# ModulWRM1470.net
KiCad netlist of a schematic drawn in Altium Designer
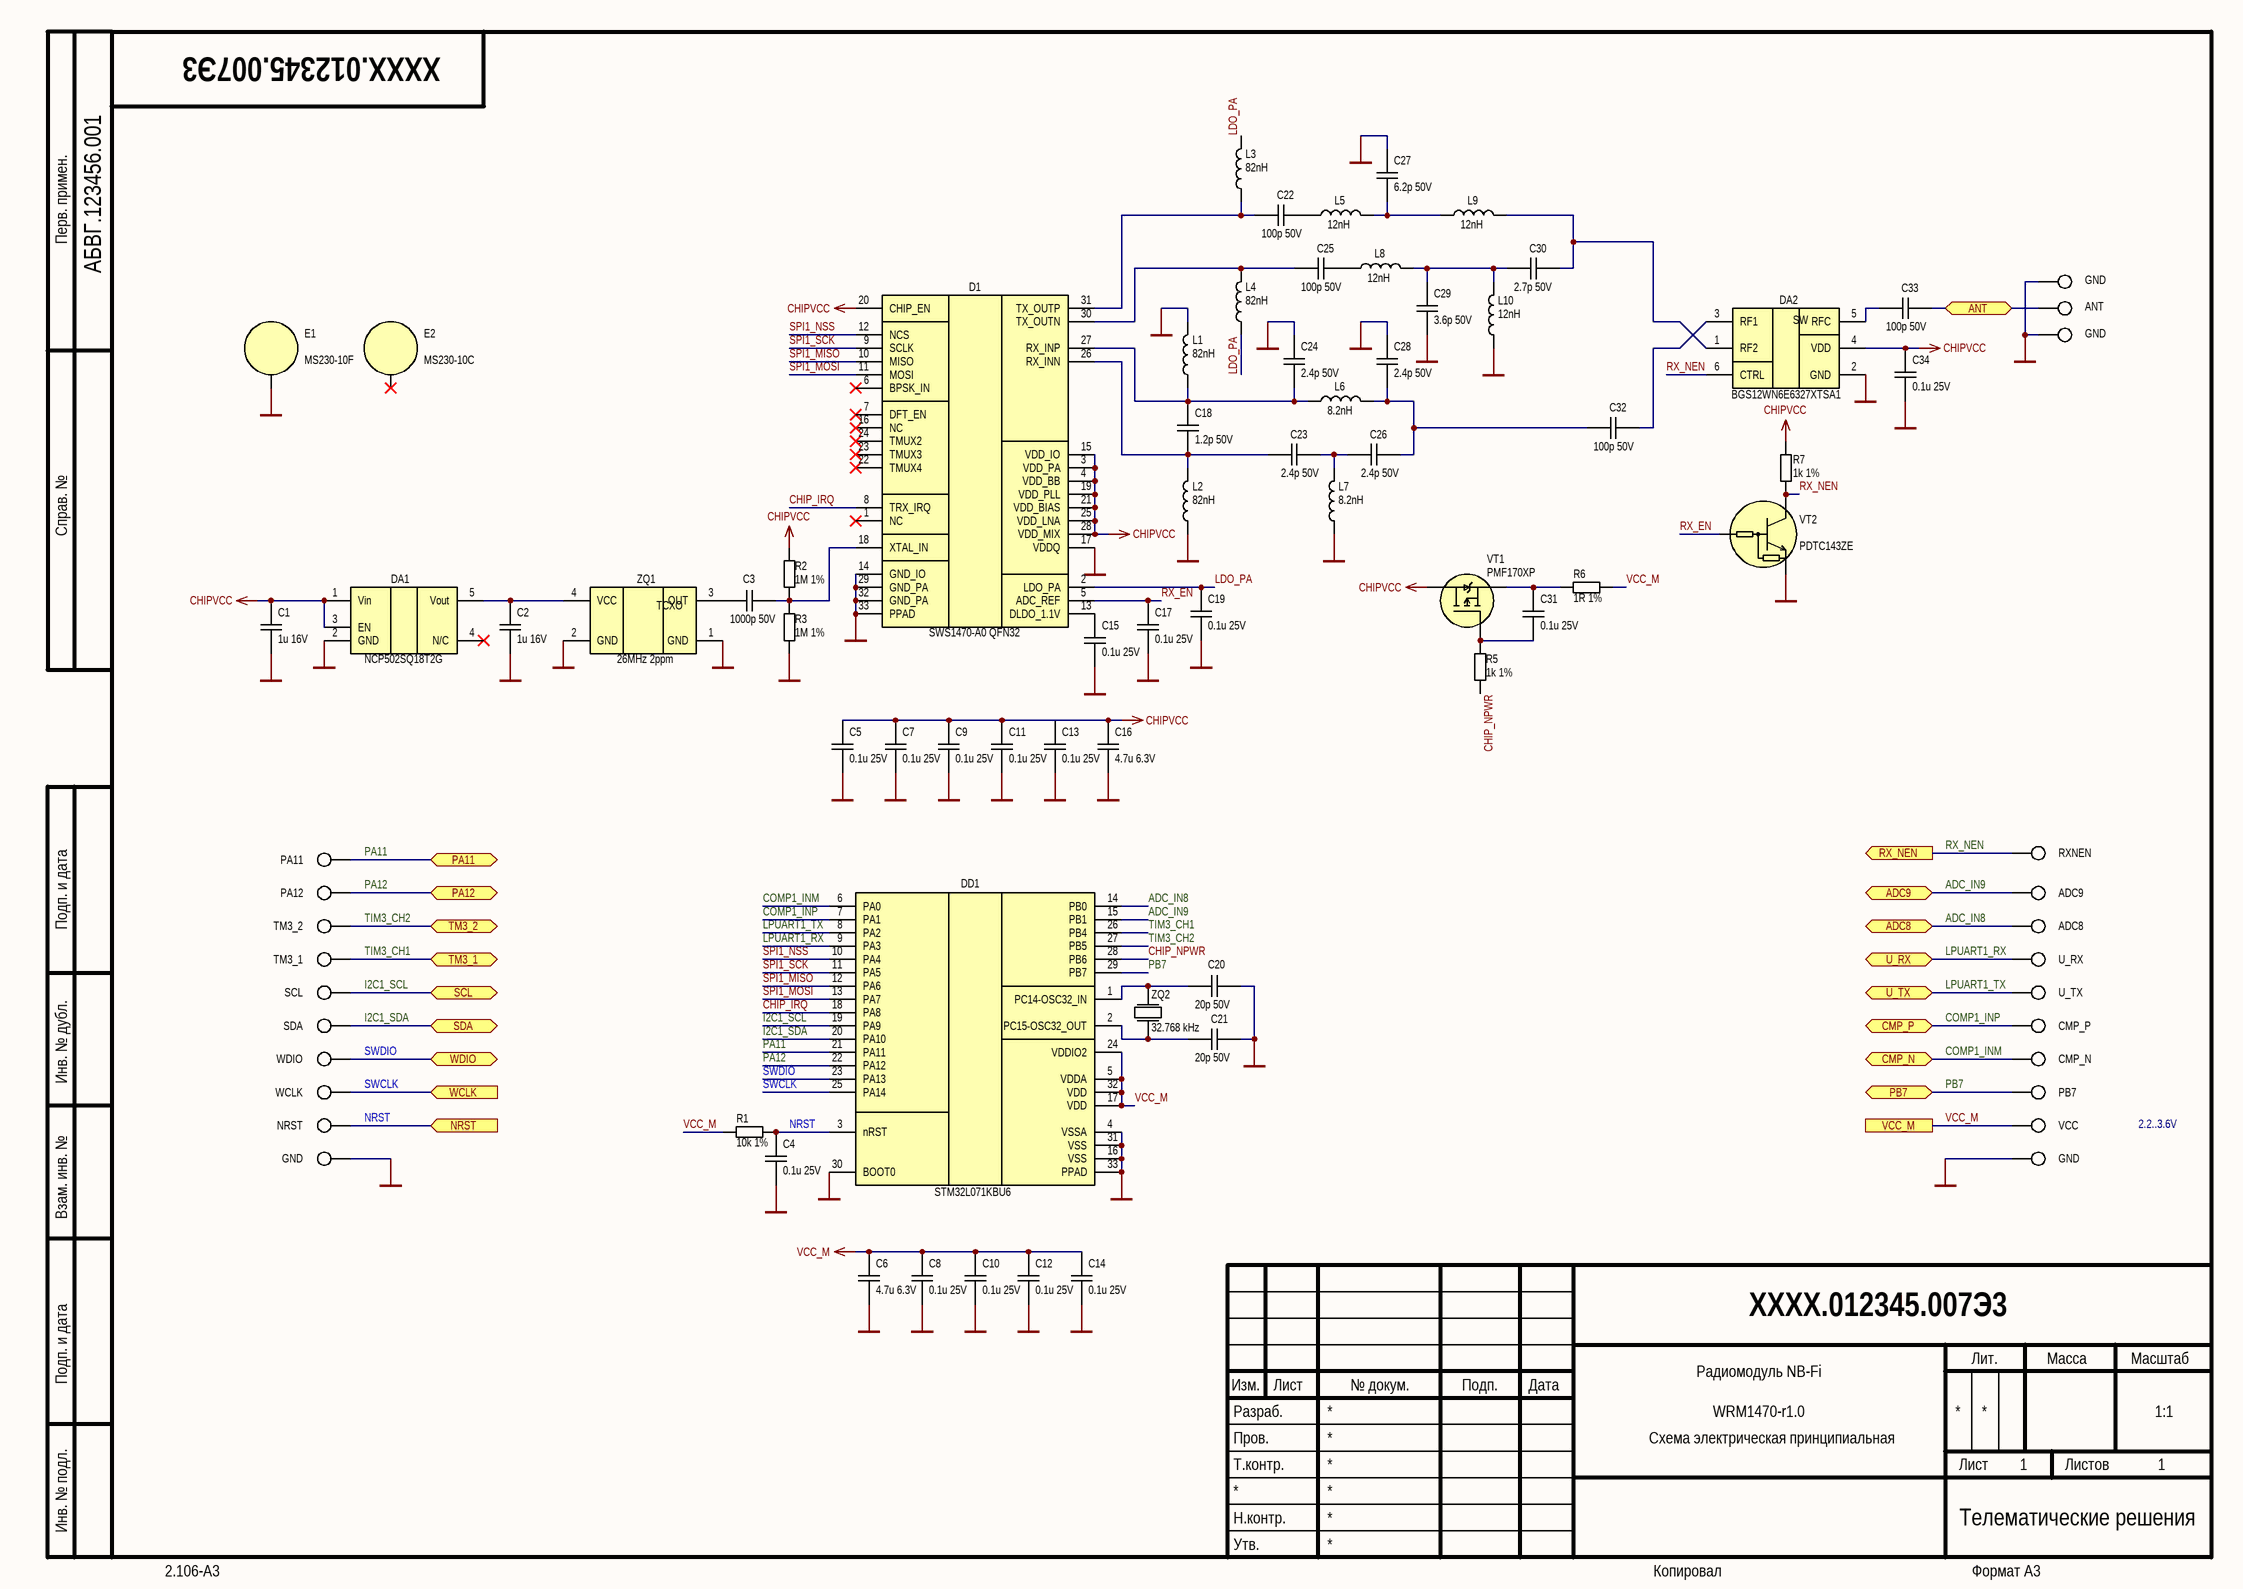
[diagram p0: ModulWRM1470.SchDoc]

(export (version "E")
  (design (tool "Eeschema 10.0.6"))
  (components
    (comp (ref "C1")
      (value "1u 16V")
      (footprint "C0402")
      (description "CAP CER 1UF 16V X5R 0402")
      (fields (field (name "PARTNUMBER") "CC0402KRX5R7BB105"))
      (libsource (lib "Capacitors") (part "CC0402KRX5R7BB105"))
    )
    (comp (ref "C2")
      (value "1u 16V")
      (footprint "C0402")
      (description "CAP CER 1UF 16V X5R 0402")
      (fields (field (name "PARTNUMBER") "CC0402KRX5R7BB105"))
      (libsource (lib "Capacitors") (part "CC0402KRX5R7BB105"))
    )
    (comp (ref "C3")
      (value "1000p 50V")
      (footprint "C0402")
      (description "CAP CER 1000PF 50V X7R 0402")
      (fields (field (name "PARTNUMBER") "CC0402JRX7R9BB102"))
      (libsource (lib "Capacitors") (part "CC0402JRX7R9BB102"))
    )
    (comp (ref "C4")
      (value "0.1u 25V")
      (footprint "C0402")
      (description "CAP CER 0.1UF 25V X7R 0402")
      (fields (field (name "PARTNUMBER") "CC0402KRX7R8BB104"))
      (libsource (lib "Capacitors") (part "CC0402KRX7R8BB104"))
    )
    (comp (ref "C5")
      (value "0.1u 25V")
      (footprint "C0402")
      (description "CAP CER 0.1UF 25V X7R 0402")
      (fields (field (name "PARTNUMBER") "CC0402KRX7R8BB104"))
      (libsource (lib "Capacitors") (part "CC0402KRX7R8BB104"))
    )
    (comp (ref "C6")
      (value "4.7u 6.3V")
      (footprint "C0402")
      (description "CAP CER 4.7UF 6.3V X5R 0402")
      (fields (field (name "PARTNUMBER") "CC0402KRX5R5BB475"))
      (libsource (lib "Capacitors") (part "CC0402KRX5R5BB475"))
    )
    (comp (ref "C7")
      (value "0.1u 25V")
      (footprint "C0402")
      (description "CAP CER 0.1UF 25V X7R 0402")
      (fields (field (name "PARTNUMBER") "CC0402KRX7R8BB104"))
      (libsource (lib "Capacitors") (part "CC0402KRX7R8BB104"))
    )
    (comp (ref "C8")
      (value "0.1u 25V")
      (footprint "C0402")
      (description "CAP CER 0.1UF 25V X7R 0402")
      (fields (field (name "PARTNUMBER") "CC0402KRX7R8BB104"))
      (libsource (lib "Capacitors") (part "CC0402KRX7R8BB104"))
    )
    (comp (ref "C9")
      (value "0.1u 25V")
      (footprint "C0402")
      (description "CAP CER 0.1UF 25V X7R 0402")
      (fields (field (name "PARTNUMBER") "CC0402KRX7R8BB104"))
      (libsource (lib "Capacitors") (part "CC0402KRX7R8BB104"))
    )
    (comp (ref "C10")
      (value "0.1u 25V")
      (footprint "C0402")
      (description "CAP CER 0.1UF 25V X7R 0402")
      (fields (field (name "PARTNUMBER") "CC0402KRX7R8BB104"))
      (libsource (lib "Capacitors") (part "CC0402KRX7R8BB104"))
    )
    (comp (ref "C11")
      (value "0.1u 25V")
      (footprint "C0402")
      (description "CAP CER 0.1UF 25V X7R 0402")
      (fields (field (name "PARTNUMBER") "CC0402KRX7R8BB104"))
      (libsource (lib "Capacitors") (part "CC0402KRX7R8BB104"))
    )
    (comp (ref "C12")
      (value "0.1u 25V")
      (footprint "C0402")
      (description "CAP CER 0.1UF 25V X7R 0402")
      (fields (field (name "PARTNUMBER") "CC0402KRX7R8BB104"))
      (libsource (lib "Capacitors") (part "CC0402KRX7R8BB104"))
    )
    (comp (ref "C13")
      (value "0.1u 25V")
      (footprint "C0402")
      (description "CAP CER 0.1UF 25V X7R 0402")
      (fields (field (name "PARTNUMBER") "CC0402KRX7R8BB104"))
      (libsource (lib "Capacitors") (part "CC0402KRX7R8BB104"))
    )
    (comp (ref "C14")
      (value "0.1u 25V")
      (footprint "C0402")
      (description "CAP CER 0.1UF 25V X7R 0402")
      (fields (field (name "PARTNUMBER") "CC0402KRX7R8BB104"))
      (libsource (lib "Capacitors") (part "CC0402KRX7R8BB104"))
    )
    (comp (ref "C15")
      (value "0.1u 25V")
      (footprint "C0402")
      (description "CAP CER 0.1UF 25V X7R 0402")
      (fields (field (name "PARTNUMBER") "CC0402KRX7R8BB104"))
      (libsource (lib "Capacitors") (part "CC0402KRX7R8BB104"))
    )
    (comp (ref "C16")
      (value "4.7u 6.3V")
      (footprint "C0402")
      (description "CAP CER 4.7UF 6.3V X5R 0402")
      (fields (field (name "PARTNUMBER") "CC0402KRX5R5BB475"))
      (libsource (lib "Capacitors") (part "CC0402KRX5R5BB475"))
    )
    (comp (ref "C17")
      (value "0.1u 25V")
      (footprint "C0402")
      (description "CAP CER 0.1UF 25V X7R 0402")
      (fields (field (name "PARTNUMBER") "CC0402KRX7R8BB104"))
      (libsource (lib "Capacitors") (part "CC0402KRX7R8BB104"))
    )
    (comp (ref "C18")
      (value "1.2p 50V")
      (footprint "C0402")
      (description "CAP CER 1.2PF 50V C0G/NPO 0402")
      (fields (field (name "PARTNUMBER") "CC0402BRNPO9BN1R2"))
      (libsource (lib "Capacitors") (part "CC0402BRNPO9BN1R2"))
    )
    (comp (ref "C19")
      (value "0.1u 25V")
      (footprint "C0402")
      (description "CAP CER 0.1UF 25V X7R 0402")
      (fields (field (name "PARTNUMBER") "CC0402KRX7R8BB104"))
      (libsource (lib "Capacitors") (part "CC0402KRX7R8BB104"))
    )
    (comp (ref "C20")
      (value "20p 50V")
      (footprint "C0402")
      (description "CAP CER 20PF 50V C0G/NPO 0402")
      (fields (field (name "PARTNUMBER") "CC0402JRNPO9BN200"))
      (libsource (lib "Capacitors") (part "CC0402JRNPO9BN200"))
    )
    (comp (ref "C21")
      (value "20p 50V")
      (footprint "C0402")
      (description "CAP CER 20PF 50V C0G/NPO 0402")
      (fields (field (name "PARTNUMBER") "CC0402JRNPO9BN200"))
      (libsource (lib "Capacitors") (part "CC0402JRNPO9BN200"))
    )
    (comp (ref "C22")
      (value "100p 50V")
      (footprint "C0402")
      (description "CAP CER 100PF 50V C0G/NPO 0402")
      (fields (field (name "PARTNUMBER") "CC0402JRNPO9BN101"))
      (libsource (lib "Capacitors") (part "CC0402JRNPO9BN101"))
    )
    (comp (ref "C23")
      (value "2.4p 50V")
      (footprint "C0402")
      (description "CAP CER 2.4PF 50V NPO 0402")
      (fields (field (name "PARTNUMBER") "CC0402BRNPO9BN2R4"))
      (libsource (lib "Capacitors") (part "CC0402BRNPO9BN2R4"))
    )
    (comp (ref "C24")
      (value "2.4p 50V")
      (footprint "C0402")
      (description "CAP CER 2.4PF 50V NPO 0402")
      (fields (field (name "PARTNUMBER") "CC0402BRNPO9BN2R4"))
      (libsource (lib "Capacitors") (part "CC0402BRNPO9BN2R4"))
    )
    (comp (ref "C25")
      (value "100p 50V")
      (footprint "C0402")
      (description "CAP CER 100PF 50V C0G/NPO 0402")
      (fields (field (name "PARTNUMBER") "CC0402JRNPO9BN101"))
      (libsource (lib "Capacitors") (part "CC0402JRNPO9BN101"))
    )
    (comp (ref "C26")
      (value "2.4p 50V")
      (footprint "C0402")
      (description "CAP CER 2.4PF 50V NPO 0402")
      (fields (field (name "PARTNUMBER") "CC0402BRNPO9BN2R4"))
      (libsource (lib "Capacitors") (part "CC0402BRNPO9BN2R4"))
    )
    (comp (ref "C27")
      (value "6.2p 50V")
      (footprint "C0402")
      (description "CAP CER 6.2PF 50V NPO 0402")
      (fields (field (name "PARTNUMBER") "CC0402CRNPO9BN6R2"))
      (libsource (lib "Capacitors") (part "CC0402CRNPO9BN6R2"))
    )
    (comp (ref "C28")
      (value "2.4p 50V")
      (footprint "C0402")
      (description "CAP CER 2.4PF 50V NPO 0402")
      (fields (field (name "PARTNUMBER") "CC0402BRNPO9BN2R4"))
      (libsource (lib "Capacitors") (part "CC0402BRNPO9BN2R4"))
    )
    (comp (ref "C29")
      (value "3.6p 50V")
      (footprint "C0402")
      (description "CAP CER 3.6PF 50V NPO 0402")
      (fields (field (name "PARTNUMBER") "CC0402BRNPO9BN3R6"))
      (libsource (lib "Capacitors") (part "CC0402BRNPO9BN3R6"))
    )
    (comp (ref "C30")
      (value "2.7p 50V")
      (footprint "C0402")
      (description "CAP CER 2.7PF 50V C0G/NPO 0402")
      (fields (field (name "PARTNUMBER") "CC0402BRNPO9BN2R7"))
      (libsource (lib "Capacitors") (part "CC0402BRNPO9BN2R7"))
    )
    (comp (ref "C31")
      (value "0.1u 25V")
      (footprint "C0402")
      (description "CAP CER 0.1UF 25V X7R 0402")
      (fields (field (name "PARTNUMBER") "CC0402KRX7R8BB104"))
      (libsource (lib "Capacitors") (part "CC0402KRX7R8BB104"))
    )
    (comp (ref "C32")
      (value "100p 50V")
      (footprint "C0402")
      (description "CAP CER 100PF 50V C0G/NPO 0402")
      (fields (field (name "PARTNUMBER") "CC0402JRNPO9BN101"))
      (libsource (lib "Capacitors") (part "CC0402JRNPO9BN101"))
    )
    (comp (ref "C33")
      (value "100p 50V")
      (footprint "C0402")
      (description "CAP CER 100PF 50V C0G/NPO 0402")
      (fields (field (name "PARTNUMBER") "CC0402JRNPO9BN101"))
      (libsource (lib "Capacitors") (part "CC0402JRNPO9BN101"))
    )
    (comp (ref "C34")
      (value "0.1u 25V")
      (footprint "C0402")
      (description "CAP CER 0.1UF 25V X7R 0402")
      (fields (field (name "PARTNUMBER") "CC0402KRX7R8BB104"))
      (libsource (lib "Capacitors") (part "CC0402KRX7R8BB104"))
    )
    (comp (ref "D1")
      (value "SWS1470-A0 QFN32")
      (footprint "QFN32")
      (description "Waviot NB-Fi RF Transceiver QFN32")
      (libsource (lib "Integrated Circuits (ICs)") (part "SWS1470-A0 QFN32"))
    )
    (comp (ref "DA1")
      (value "NCP502SQ18T2G")
      (footprint "SOT323-5")
      (description "IC REG LINEAR 1.8V 80MA SC88A")
      (libsource (lib "Integrated Circuits (ICs)") (part "NCP502SQ18T2G"))
    )
    (comp (ref "DA2")
      (value "BGS12WN6E6327XTSA1")
      (footprint "6-XFDFN")
      (description "RF Switch IC WLAN SPDT 50Ohm PG-TSNP-6-10")
      (libsource (lib "RF, IF and RFID") (part "BGS12WN6E6327XTSA1"))
    )
    (comp (ref "DD1")
      (value "STM32L071KBU6")
      (footprint "UFQFPN32")
      (description "ARM® Cortex®-M0+ STM32L0 Microcontroller IC 32-Bit 32MHz 128KB (128K x 8) FLASH 32-UFQFPN (5x5)")
      (libsource (lib "Integrated Circuits (ICs)") (part "STM32L071KBU6"))
    )
    (comp (ref "E1")
      (value "MS230-10F")
      (footprint "MS230-10F")
      (description "RF SHLD FRAME 0.461\"X0.906\" SLDR")
      (libsource (lib "RF, IF and RFID") (part "MS230-10F"))
    )
    (comp (ref "E2")
      (value "MS230-10C")
      (footprint "MS230-10C")
      (description "RF SHIELD 0.461\"X0.906\" SNAP FIT")
      (libsource (lib "RF, IF and RFID") (part "MS230-10C"))
    )
    (comp (ref "L1")
      (value "82nH")
      (footprint "L0402_LQW")
      (description "FIXED IND 82NH 130MA 2.24 OHM")
      (fields (field (name "PARTNUMBER") "LQW15AN82NG00D"))
      (libsource (lib "Inductors, Coils, Chokes") (part "LQW15AN82NG00D"))
    )
    (comp (ref "L2")
      (value "82nH")
      (footprint "L0402_LQW")
      (description "FIXED IND 82NH 130MA 2.24 OHM")
      (fields (field (name "PARTNUMBER") "LQW15AN82NG00D"))
      (libsource (lib "Inductors, Coils, Chokes") (part "LQW15AN82NG00D"))
    )
    (comp (ref "L3")
      (value "82nH")
      (footprint "L0402_LQW")
      (description "FIXED IND 82NH 130MA 2.24 OHM")
      (fields (field (name "PARTNUMBER") "LQW15AN82NG00D"))
      (libsource (lib "Inductors, Coils, Chokes") (part "LQW15AN82NG00D"))
    )
    (comp (ref "L4")
      (value "82nH")
      (footprint "L0402_LQW")
      (description "FIXED IND 82NH 130MA 2.24 OHM")
      (fields (field (name "PARTNUMBER") "LQW15AN82NG00D"))
      (libsource (lib "Inductors, Coils, Chokes") (part "LQW15AN82NG00D"))
    )
    (comp (ref "L5")
      (value "12nH")
      (footprint "L0402_LQW")
      (description "FIXED IND 12NH 500MA 140 MOHM")
      (fields (field (name "PARTNUMBER") "LQW15AN12NG00D"))
      (libsource (lib "Inductors, Coils, Chokes") (part "LQW15AN12NG00D"))
    )
    (comp (ref "L6")
      (value "8.2nH")
      (footprint "L0402_LQW")
      (description "FIXED IND 8.2NH 540MA 140 MOHM")
      (fields (field (name "PARTNUMBER") "LQW15AN8N2G00D"))
      (libsource (lib "Inductors, Coils, Chokes") (part "LQW15AN8N2G00D"))
    )
    (comp (ref "L7")
      (value "8.2nH")
      (footprint "L0402_LQW")
      (description "FIXED IND 8.2NH 540MA 140 MOHM")
      (fields (field (name "PARTNUMBER") "LQW15AN8N2G00D"))
      (libsource (lib "") (part "LQW15AN8N2G00D_1"))
    )
    (comp (ref "L8")
      (value "12nH")
      (footprint "L0402_LQW")
      (description "FIXED IND 12NH 500MA 140 MOHM")
      (fields (field (name "PARTNUMBER") "LQW15AN12NG00D"))
      (libsource (lib "Inductors, Coils, Chokes") (part "LQW15AN12NG00D"))
    )
    (comp (ref "L9")
      (value "12nH")
      (footprint "L0402_LQW")
      (description "FIXED IND 12NH 500MA 140 MOHM")
      (fields (field (name "PARTNUMBER") "LQW15AN12NG00D"))
      (libsource (lib "Inductors, Coils, Chokes") (part "LQW15AN12NG00D"))
    )
    (comp (ref "L10")
      (value "12nH")
      (footprint "L0402_LQW")
      (description "FIXED IND 12NH 500MA 140 MOHM")
      (fields (field (name "PARTNUMBER") "LQW15AN12NG00D"))
      (libsource (lib "") (part "LQW15AN12NG00D_1"))
    )
    (comp (ref "R1")
      (value "10k 1%")
      (footprint "R0402")
      (description "RES SMD 10K OHM 1% 1/16W 0402")
      (fields (field (name "PARTNUMBER") "RC0402FR-0710KL"))
      (libsource (lib "Resistors") (part "RC0402FR-0710KL"))
    )
    (comp (ref "R2")
      (value "1M 1%")
      (footprint "R0402")
      (description "RES SMD 1M OHM 1% 1/16W 0402")
      (fields (field (name "PARTNUMBER") "RC0402FR-071ML"))
      (libsource (lib "Resistors") (part "RC0402FR-071ML"))
    )
    (comp (ref "R3")
      (value "1M 1%")
      (footprint "R0402")
      (description "RES SMD 1M OHM 1% 1/16W 0402")
      (fields (field (name "PARTNUMBER") "RC0402FR-071ML"))
      (libsource (lib "Resistors") (part "RC0402FR-071ML"))
    )
    (comp (ref "R5")
      (value "1k 1%")
      (footprint "R0402")
      (description "RES SMD 1K OHM 1% 1/16W 0402")
      (fields (field (name "PARTNUMBER") "RC0402FR-071KL"))
      (libsource (lib "Resistors") (part "RC0402FR-071KL"))
    )
    (comp (ref "R6")
      (value "1R 1%")
      (footprint "R0402")
      (description "RES SMD 1 OHM 1% 1/16W 0402")
      (fields (field (name "PARTNUMBER") "RC0402FR-071RL"))
      (libsource (lib "Resistors") (part "RC0402FR-071RL"))
    )
    (comp (ref "R7")
      (value "1k 1%")
      (footprint "R0402")
      (description "RES SMD 1K OHM 1% 1/16W 0402")
      (fields (field (name "PARTNUMBER") "RC0402FR-071KL"))
      (libsource (lib "Resistors") (part "RC0402FR-071KL"))
    )
    (comp (ref "VT1")
      (value "PMF170XP")
      (footprint "SOT323")
      (description "MOSFET P-CH 20V 1A SOT323")
      (libsource (lib "Discrete Semiconductor Products") (part "PMF170XP"))
    )
    (comp (ref "VT2")
      (value "PDTC143ZE")
      (footprint "SOT416")
      (description "SMALL SIGNAL BIPOLAR TRANSISTOR")
      (libsource (lib "Discrete Semiconductor Products") (part "PDTC143ZE"))
    )
    (comp (ref "XT1")
      (value "PA11")
      (footprint "PAD-d0.6-x1.1-y1.2")
      (libsource (lib "Special") (part "PIN"))
    )
    (comp (ref "XT2")
      (value "PA12")
      (footprint "PAD-d0.6-x1.1-y1.2")
      (libsource (lib "Special") (part "PIN"))
    )
    (comp (ref "XT3")
      (value "TM3_2")
      (footprint "PAD-d0.6-x1.1-y1.2")
      (libsource (lib "Special") (part "PIN"))
    )
    (comp (ref "XT4")
      (value "TM3_1")
      (footprint "PAD-d0.6-x1.1-y1.2")
      (libsource (lib "Special") (part "PIN"))
    )
    (comp (ref "XT5") (value "SCL") (footprint "PAD-d0.6-x1.1-y1.2") (libsource (lib "Special") (part "PIN")))
    (comp (ref "XT6") (value "SDA") (footprint "PAD-d0.6-x1.1-y1.2") (libsource (lib "Special") (part "PIN")))
    (comp (ref "XT7")
      (value "WDIO")
      (footprint "PAD-d0.6-x1.1-y1.2")
      (libsource (lib "Special") (part "PIN"))
    )
    (comp (ref "XT8")
      (value "WCLK")
      (footprint "PAD-d0.6-x1.1-y1.2")
      (libsource (lib "Special") (part "PIN"))
    )
    (comp (ref "XT9")
      (value "NRST")
      (footprint "PAD-d0.6-x1.1-y1.2")
      (libsource (lib "Special") (part "PIN"))
    )
    (comp (ref "XT10")
      (value "GND")
      (footprint "PAD-d0.6-x1.1-y1.2")
      (libsource (lib "Special") (part "PIN"))
    )
    (comp (ref "XT11")
      (value "GND")
      (footprint "PAD-d0.6-x1.1-y1.2")
      (libsource (lib "Special") (part "PIN"))
    )
    (comp (ref "XT12")
      (value "VCC")
      (footprint "PAD-d0.6-x1.1-y1.2")
      (libsource (lib "Special") (part "PIN"))
    )
    (comp (ref "XT13")
      (value "PB7")
      (footprint "PAD-d0.6-x1.1-y1.2")
      (libsource (lib "Special") (part "PIN"))
    )
    (comp (ref "XT14")
      (value "CMP_N")
      (footprint "PAD-d0.6-x1.1-y1.2")
      (libsource (lib "Special") (part "PIN"))
    )
    (comp (ref "XT15")
      (value "CMP_P")
      (footprint "PAD-d0.6-x1.1-y1.2")
      (libsource (lib "Special") (part "PIN"))
    )
    (comp (ref "XT16")
      (value "U_TX")
      (footprint "PAD-d0.6-x1.1-y1.2")
      (libsource (lib "Special") (part "PIN"))
    )
    (comp (ref "XT17")
      (value "U_RX")
      (footprint "PAD-d0.6-x1.1-y1.2")
      (libsource (lib "Special") (part "PIN"))
    )
    (comp (ref "XT18")
      (value "ADC8")
      (footprint "PAD-d0.6-x1.1-y1.2")
      (libsource (lib "Special") (part "PIN"))
    )
    (comp (ref "XT19")
      (value "ADC9")
      (footprint "PAD-d0.6-x1.1-y1.2")
      (libsource (lib "Special") (part "PIN"))
    )
    (comp (ref "XT20")
      (value "RXNEN")
      (footprint "PAD-d0.6-x1.1-y1.2")
      (libsource (lib "Special") (part "PIN"))
    )
    (comp (ref "XT21")
      (value "GND")
      (footprint "PAD-d0.6-x1.1-y1.2")
      (libsource (lib "Special") (part "PIN"))
    )
    (comp (ref "XT22")
      (value "ANT")
      (footprint "PAD-d0.6-x1.1-y1.2")
      (libsource (lib "Special") (part "PIN"))
    )
    (comp (ref "XT23")
      (value "GND")
      (footprint "PAD-d0.6-x1.1-y1.2")
      (libsource (lib "Special") (part "PIN"))
    )
    (comp (ref "ZQ1")
      (value "26MHz 2ppm")
      (footprint "QSMD2.0x1.6x0.7")
      (description "TCXO Oscillator 4-pin")
      (fields (field (name "PARTNUMBER") "NT2016SA-26.000000MHZ-NBG2"))
      (libsource (lib "Crystals, Oscillators, Resonators") (part "NT2016SA-26.000000MHZ-NBG2"))
    )
    (comp (ref "ZQ2")
      (value "32.768 kHz")
      (footprint "QSMD3.2X1.5X0.8")
      (description "CRYSTAL 32.768KHZ 12.5PF SMD")
      (fields (field (name "PARTNUMBER") "NX3215SA-32.768K-EXS00A"))
      (libsource (lib "Crystals, Oscillators, Resonators") (part "NX3215SA-32.768K-EXS00A"))
    )
  )
  (nets
    (net (code "1") (name "/ADC_IN8") (class "Default")
      (node (ref "DD1") (pin "14") (pinfunction "PB0_14") (pintype "passive"))
      (node (ref "XT18") (pin "1") (pinfunction "1_1") (pintype "passive"))
    )
    (net (code "2") (name "/ADC_IN9") (class "Default")
      (node (ref "DD1") (pin "15") (pinfunction "PB1_15") (pintype "passive"))
      (node (ref "XT19") (pin "1") (pinfunction "1_1") (pintype "passive"))
    )
    (net (code "3") (name "/ANT") (class "Default")
      (node (ref "C33") (pin "2") (pinfunction "2_2") (pintype "passive"))
      (node (ref "XT22") (pin "1") (pinfunction "1_1") (pintype "passive"))
    )
    (net (code "4") (name "/CHIP_IRQ") (class "Default")
      (node (ref "D1") (pin "8") (pinfunction "TRX_IRQ_8") (pintype "passive"))
      (node (ref "DD1") (pin "18") (pinfunction "PA8_18") (pintype "passive"))
    )
    (net (code "5") (name "/CHIP_NPWR") (class "Default")
      (node (ref "DD1") (pin "28") (pinfunction "PB6_28") (pintype "passive"))
      (node (ref "R5") (pin "1") (pinfunction "1_1") (pintype "passive"))
    )
    (net (code "6") (name "/COMP1_INM") (class "Default")
      (node (ref "DD1") (pin "6") (pinfunction "PA0_6") (pintype "passive"))
      (node (ref "XT14") (pin "1") (pinfunction "1_1") (pintype "passive"))
    )
    (net (code "7") (name "/COMP1_INP") (class "Default")
      (node (ref "DD1") (pin "7") (pinfunction "PA1_7") (pintype "passive"))
      (node (ref "XT15") (pin "1") (pinfunction "1_1") (pintype "passive"))
    )
    (net (code "8") (name "/I2C1_SCL") (class "Default")
      (node (ref "DD1") (pin "19") (pinfunction "PA9_19") (pintype "passive"))
      (node (ref "XT5") (pin "1") (pinfunction "1_1") (pintype "passive"))
    )
    (net (code "9") (name "/I2C1_SDA") (class "Default")
      (node (ref "DD1") (pin "20") (pinfunction "PA10_20") (pintype "passive"))
      (node (ref "XT6") (pin "1") (pinfunction "1_1") (pintype "passive"))
    )
    (net (code "10") (name "/LDO_PA") (class "Default")
      (node (ref "C19") (pin "2") (pinfunction "2_2") (pintype "passive"))
      (node (ref "D1") (pin "2") (pinfunction "LDO_PA_2") (pintype "passive"))
      (node (ref "L3") (pin "2") (pinfunction "2_2") (pintype "passive"))
      (node (ref "L4") (pin "1") (pinfunction "1_1") (pintype "passive"))
    )
    (net (code "11") (name "/LPUART1_RX") (class "Default")
      (node (ref "DD1") (pin "9") (pinfunction "PA3_9") (pintype "passive"))
      (node (ref "XT17") (pin "1") (pinfunction "1_1") (pintype "passive"))
    )
    (net (code "12") (name "/LPUART1_TX") (class "Default")
      (node (ref "DD1") (pin "8") (pinfunction "PA2_8") (pintype "passive"))
      (node (ref "XT16") (pin "1") (pinfunction "1_1") (pintype "passive"))
    )
    (net (code "13") (name "/NRST") (class "Default")
      (node (ref "C4") (pin "1") (pinfunction "1_1") (pintype "passive"))
      (node (ref "DD1") (pin "3") (pinfunction "nRST_3") (pintype "passive"))
      (node (ref "R1") (pin "2") (pinfunction "2_2") (pintype "passive"))
      (node (ref "XT9") (pin "1") (pinfunction "1_1") (pintype "passive"))
    )
    (net (code "14") (name "/PA11") (class "Default")
      (node (ref "DD1") (pin "21") (pinfunction "PA11_21") (pintype "passive"))
      (node (ref "XT1") (pin "1") (pinfunction "1_1") (pintype "passive"))
    )
    (net (code "15") (name "/PA12") (class "Default")
      (node (ref "DD1") (pin "22") (pinfunction "PA12_22") (pintype "passive"))
      (node (ref "XT2") (pin "1") (pinfunction "1_1") (pintype "passive"))
    )
    (net (code "16") (name "/PB7") (class "Default")
      (node (ref "DD1") (pin "29") (pinfunction "PB7_29") (pintype "passive"))
      (node (ref "XT13") (pin "1") (pinfunction "1_1") (pintype "passive"))
    )
    (net (code "17") (name "/RX_EN") (class "Default")
      (node (ref "C17") (pin "2") (pinfunction "2_2") (pintype "passive"))
      (node (ref "D1") (pin "5") (pinfunction "ADC_REF_5") (pintype "passive"))
      (node (ref "VT2") (pin "1") (pinfunction "1_1") (pintype "passive"))
    )
    (net (code "18") (name "/RX_NEN") (class "Default")
      (node (ref "DA2") (pin "6") (pinfunction "CTRL_6") (pintype "passive"))
      (node (ref "R7") (pin "1") (pinfunction "1_1") (pintype "passive"))
      (node (ref "VT2") (pin "3") (pinfunction "3_3") (pintype "passive"))
      (node (ref "XT20") (pin "1") (pinfunction "1_1") (pintype "passive"))
    )
    (net (code "19") (name "/SPI1_MISO") (class "Default")
      (node (ref "D1") (pin "10") (pinfunction "MISO_10") (pintype "passive"))
      (node (ref "DD1") (pin "12") (pinfunction "PA6_12") (pintype "passive"))
    )
    (net (code "20") (name "/SPI1_MOSI") (class "Default")
      (node (ref "D1") (pin "11") (pinfunction "MOSI_11") (pintype "passive"))
      (node (ref "DD1") (pin "13") (pinfunction "PA7_13") (pintype "passive"))
    )
    (net (code "21") (name "/SPI1_NSS") (class "Default")
      (node (ref "D1") (pin "12") (pinfunction "NCS_12") (pintype "passive"))
      (node (ref "DD1") (pin "10") (pinfunction "PA4_10") (pintype "passive"))
    )
    (net (code "22") (name "/SPI1_SCK") (class "Default")
      (node (ref "D1") (pin "9") (pinfunction "SCLK_9") (pintype "passive"))
      (node (ref "DD1") (pin "11") (pinfunction "PA5_11") (pintype "passive"))
    )
    (net (code "23") (name "/SWCLK") (class "Default")
      (node (ref "DD1") (pin "25") (pinfunction "PA14_25") (pintype "passive"))
      (node (ref "XT8") (pin "1") (pinfunction "1_1") (pintype "passive"))
    )
    (net (code "24") (name "/SWDIO") (class "Default")
      (node (ref "DD1") (pin "23") (pinfunction "PA13_23") (pintype "passive"))
      (node (ref "XT7") (pin "1") (pinfunction "1_1") (pintype "passive"))
    )
    (net (code "25") (name "/TIM3_CH1") (class "Default")
      (node (ref "DD1") (pin "26") (pinfunction "PB4_26") (pintype "passive"))
      (node (ref "XT4") (pin "1") (pinfunction "1_1") (pintype "passive"))
    )
    (net (code "26") (name "/TIM3_CH2") (class "Default")
      (node (ref "DD1") (pin "27") (pinfunction "PB5_27") (pintype "passive"))
      (node (ref "XT3") (pin "1") (pinfunction "1_1") (pintype "passive"))
    )
    (net (code "27") (name "CHIPVCC") (class "Default")
      (node (ref "C1") (pin "2") (pinfunction "2_2") (pintype "passive"))
      (node (ref "C11") (pin "2") (pinfunction "2_2") (pintype "passive"))
      (node (ref "C13") (pin "2") (pinfunction "2_2") (pintype "passive"))
      (node (ref "C16") (pin "2") (pinfunction "2_2") (pintype "passive"))
      (node (ref "C34") (pin "2") (pinfunction "2_2") (pintype "passive"))
      (node (ref "C5") (pin "2") (pinfunction "2_2") (pintype "passive"))
      (node (ref "C7") (pin "2") (pinfunction "2_2") (pintype "passive"))
      (node (ref "C9") (pin "2") (pinfunction "2_2") (pintype "passive"))
      (node (ref "D1") (pin "15") (pinfunction "VDD_IO_15") (pintype "passive"))
      (node (ref "D1") (pin "19") (pinfunction "VDD_PLL_19") (pintype "passive"))
      (node (ref "D1") (pin "20") (pinfunction "CHIP_EN_20") (pintype "passive"))
      (node (ref "D1") (pin "21") (pinfunction "VDD_BIAS_21") (pintype "passive"))
      (node (ref "D1") (pin "25") (pinfunction "VDD_LNA_25") (pintype "passive"))
      (node (ref "D1") (pin "28") (pinfunction "VDD_MIX_28") (pintype "passive"))
      (node (ref "D1") (pin "3") (pinfunction "VDD_PA_3") (pintype "passive"))
      (node (ref "D1") (pin "4") (pinfunction "VDD_BB_4") (pintype "passive"))
      (node (ref "DA1") (pin "1") (pinfunction "Vin_1") (pintype "passive"))
      (node (ref "DA1") (pin "3") (pinfunction "EN_3") (pintype "passive"))
      (node (ref "DA2") (pin "4") (pinfunction "VDD_4") (pintype "passive"))
      (node (ref "R2") (pin "2") (pinfunction "2_2") (pintype "passive"))
      (node (ref "R7") (pin "2") (pinfunction "2_2") (pintype "passive"))
      (node (ref "VT1") (pin "3") (pinfunction "D_3") (pintype "passive"))
    )
    (net (code "28") (name "GND") (class "Default")
      (node (ref "C1") (pin "1") (pinfunction "1_1") (pintype "passive"))
      (node (ref "C10") (pin "2") (pinfunction "2_2") (pintype "passive"))
      (node (ref "C11") (pin "1") (pinfunction "1_1") (pintype "passive"))
      (node (ref "C12") (pin "2") (pinfunction "2_2") (pintype "passive"))
      (node (ref "C13") (pin "1") (pinfunction "1_1") (pintype "passive"))
      (node (ref "C14") (pin "2") (pinfunction "2_2") (pintype "passive"))
      (node (ref "C15") (pin "1") (pinfunction "1_1") (pintype "passive"))
      (node (ref "C16") (pin "1") (pinfunction "1_1") (pintype "passive"))
      (node (ref "C17") (pin "1") (pinfunction "1_1") (pintype "passive"))
      (node (ref "C19") (pin "1") (pinfunction "1_1") (pintype "passive"))
      (node (ref "C2") (pin "1") (pinfunction "1_1") (pintype "passive"))
      (node (ref "C20") (pin "2") (pinfunction "2_2") (pintype "passive"))
      (node (ref "C21") (pin "2") (pinfunction "2_2") (pintype "passive"))
      (node (ref "C24") (pin "1") (pinfunction "1_1") (pintype "passive"))
      (node (ref "C27") (pin "1") (pinfunction "1_1") (pintype "passive"))
      (node (ref "C28") (pin "1") (pinfunction "1_1") (pintype "passive"))
      (node (ref "C29") (pin "2") (pinfunction "2_2") (pintype "passive"))
      (node (ref "C34") (pin "1") (pinfunction "1_1") (pintype "passive"))
      (node (ref "C4") (pin "2") (pinfunction "2_2") (pintype "passive"))
      (node (ref "C5") (pin "1") (pinfunction "1_1") (pintype "passive"))
      (node (ref "C6") (pin "2") (pinfunction "2_2") (pintype "passive"))
      (node (ref "C7") (pin "1") (pinfunction "1_1") (pintype "passive"))
      (node (ref "C8") (pin "2") (pinfunction "2_2") (pintype "passive"))
      (node (ref "C9") (pin "1") (pinfunction "1_1") (pintype "passive"))
      (node (ref "D1") (pin "14") (pinfunction "GND_IO_14") (pintype "passive"))
      (node (ref "D1") (pin "17") (pinfunction "VDDQ_17") (pintype "passive"))
      (node (ref "D1") (pin "29") (pinfunction "GND_PA_29") (pintype "passive"))
      (node (ref "D1") (pin "32") (pinfunction "GND_PA_32") (pintype "passive"))
      (node (ref "D1") (pin "33") (pinfunction "PPAD_33") (pintype "passive"))
      (node (ref "DA1") (pin "2") (pinfunction "GND_2") (pintype "passive"))
      (node (ref "DA2") (pin "2") (pinfunction "GND_2") (pintype "passive"))
      (node (ref "DD1") (pin "16") (pinfunction "VSS_16") (pintype "power_in"))
      (node (ref "DD1") (pin "30") (pinfunction "BOOT0_30") (pintype "passive"))
      (node (ref "DD1") (pin "31") (pinfunction "VSS_31") (pintype "power_in"))
      (node (ref "DD1") (pin "33") (pinfunction "PPAD_33") (pintype "power_in"))
      (node (ref "DD1") (pin "4") (pinfunction "VSSA_4") (pintype "power_in"))
      (node (ref "E1") (pin "1") (pinfunction "SHIELD_1") (pintype "passive"))
      (node (ref "L1") (pin "2") (pinfunction "2_2") (pintype "passive"))
      (node (ref "L10") (pin "1") (pinfunction "1_1") (pintype "passive"))
      (node (ref "L2") (pin "1") (pinfunction "1_1") (pintype "passive"))
      (node (ref "L7") (pin "1") (pinfunction "1_1") (pintype "passive"))
      (node (ref "R3") (pin "1") (pinfunction "1_1") (pintype "passive"))
      (node (ref "VT2") (pin "2") (pinfunction "2_2") (pintype "passive"))
      (node (ref "XT10") (pin "1") (pinfunction "1_1") (pintype "passive"))
      (node (ref "XT11") (pin "1") (pinfunction "1_1") (pintype "passive"))
      (node (ref "XT21") (pin "1") (pinfunction "1_1") (pintype "passive"))
      (node (ref "XT23") (pin "1") (pinfunction "1_1") (pintype "passive"))
      (node (ref "ZQ1") (pin "1") (pinfunction "GND_1") (pintype "passive"))
      (node (ref "ZQ1") (pin "2") (pinfunction "GND_2") (pintype "passive"))
    )
    (net (code "29") (name "Net-(C22-Pad2)") (class "Default")
      (node (ref "C22") (pin "2") (pinfunction "2_2") (pintype "passive"))
      (node (ref "L5") (pin "1") (pinfunction "1_1") (pintype "passive"))
    )
    (net (code "30") (name "Net-(C23-Pad2)") (class "Default")
      (node (ref "C23") (pin "2") (pinfunction "2_2") (pintype "passive"))
      (node (ref "C26") (pin "1") (pinfunction "1_1") (pintype "passive"))
      (node (ref "L7") (pin "2") (pinfunction "2_2") (pintype "passive"))
    )
    (net (code "31") (name "Net-(C25-Pad2)") (class "Default")
      (node (ref "C25") (pin "2") (pinfunction "2_2") (pintype "passive"))
      (node (ref "L8") (pin "1") (pinfunction "1_1") (pintype "passive"))
    )
    (net (code "32") (name "Net-(C26-Pad2)") (class "Default")
      (node (ref "C26") (pin "2") (pinfunction "2_2") (pintype "passive"))
      (node (ref "C28") (pin "2") (pinfunction "2_2") (pintype "passive"))
      (node (ref "C32") (pin "1") (pinfunction "1_1") (pintype "passive"))
      (node (ref "L6") (pin "2") (pinfunction "2_2") (pintype "passive"))
    )
    (net (code "33") (name "Net-(C27-Pad2)") (class "Default")
      (node (ref "C27") (pin "2") (pinfunction "2_2") (pintype "passive"))
      (node (ref "L5") (pin "2") (pinfunction "2_2") (pintype "passive"))
      (node (ref "L9") (pin "1") (pinfunction "1_1") (pintype "passive"))
    )
    (net (code "34") (name "Net-(C29-Pad1)") (class "Default")
      (node (ref "C29") (pin "1") (pinfunction "1_1") (pintype "passive"))
      (node (ref "C30") (pin "1") (pinfunction "1_1") (pintype "passive"))
      (node (ref "L10") (pin "2") (pinfunction "2_2") (pintype "passive"))
      (node (ref "L8") (pin "2") (pinfunction "2_2") (pintype "passive"))
    )
    (net (code "35") (name "Net-(D1-DLDO_1.1V)") (class "Default")
      (node (ref "C15") (pin "2") (pinfunction "2_2") (pintype "passive"))
      (node (ref "D1") (pin "13") (pinfunction "DLDO_1.1V_13") (pintype "passive"))
    )
    (net (code "36") (name "Net-(D1-RX_INN)") (class "Default")
      (node (ref "C18") (pin "2") (pinfunction "2_2") (pintype "passive"))
      (node (ref "C23") (pin "1") (pinfunction "1_1") (pintype "passive"))
      (node (ref "D1") (pin "26") (pinfunction "RX_INN_26") (pintype "passive"))
      (node (ref "L2") (pin "2") (pinfunction "2_2") (pintype "passive"))
    )
    (net (code "37") (name "Net-(D1-RX_INP)") (class "Default")
      (node (ref "C18") (pin "1") (pinfunction "1_1") (pintype "passive"))
      (node (ref "C24") (pin "2") (pinfunction "2_2") (pintype "passive"))
      (node (ref "D1") (pin "27") (pinfunction "RX_INP_27") (pintype "passive"))
      (node (ref "L1") (pin "1") (pinfunction "1_1") (pintype "passive"))
      (node (ref "L6") (pin "1") (pinfunction "1_1") (pintype "passive"))
    )
    (net (code "38") (name "Net-(D1-TX_OUTN)") (class "Default")
      (node (ref "C25") (pin "1") (pinfunction "1_1") (pintype "passive"))
      (node (ref "D1") (pin "30") (pinfunction "TX_OUTN_30") (pintype "passive"))
      (node (ref "L4") (pin "2") (pinfunction "2_2") (pintype "passive"))
    )
    (net (code "39") (name "Net-(D1-TX_OUTP)") (class "Default")
      (node (ref "C22") (pin "1") (pinfunction "1_1") (pintype "passive"))
      (node (ref "D1") (pin "31") (pinfunction "TX_OUTP_31") (pintype "passive"))
      (node (ref "L3") (pin "1") (pinfunction "1_1") (pintype "passive"))
    )
    (net (code "40") (name "Net-(D1-XTAL_IN)") (class "Default")
      (node (ref "C3") (pin "2") (pinfunction "2_2") (pintype "passive"))
      (node (ref "D1") (pin "18") (pinfunction "XTAL_IN_18") (pintype "passive"))
      (node (ref "R2") (pin "1") (pinfunction "1_1") (pintype "passive"))
      (node (ref "R3") (pin "2") (pinfunction "2_2") (pintype "passive"))
    )
    (net (code "41") (name "Net-(DA1-Vout)") (class "Default")
      (node (ref "C2") (pin "2") (pinfunction "2_2") (pintype "passive"))
      (node (ref "DA1") (pin "5") (pinfunction "Vout_5") (pintype "passive"))
      (node (ref "ZQ1") (pin "4") (pinfunction "VCC_4") (pintype "passive"))
    )
    (net (code "42") (name "Net-(DA2-RF1)") (class "Default")
      (node (ref "C32") (pin "2") (pinfunction "2_2") (pintype "passive"))
      (node (ref "DA2") (pin "3") (pinfunction "RF1_3") (pintype "passive"))
    )
    (net (code "43") (name "Net-(DA2-RF2)") (class "Default")
      (node (ref "C30") (pin "2") (pinfunction "2_2") (pintype "passive"))
      (node (ref "DA2") (pin "1") (pinfunction "RF2_1") (pintype "passive"))
      (node (ref "L9") (pin "2") (pinfunction "2_2") (pintype "passive"))
    )
    (net (code "44") (name "Net-(DA2-RFC)") (class "Default")
      (node (ref "C33") (pin "1") (pinfunction "1_1") (pintype "passive"))
      (node (ref "DA2") (pin "5") (pinfunction "RFC_5") (pintype "passive"))
    )
    (net (code "45") (name "Net-(DD1-PC14-OSC32_IN)") (class "Default")
      (node (ref "C20") (pin "1") (pinfunction "1_1") (pintype "passive"))
      (node (ref "DD1") (pin "1") (pinfunction "PC14-OSC32_IN_1") (pintype "passive"))
      (node (ref "ZQ2") (pin "1") (pinfunction "1_1") (pintype "passive"))
    )
    (net (code "46") (name "Net-(DD1-PC15-OSC32_OUT)") (class "Default")
      (node (ref "C21") (pin "1") (pinfunction "1_1") (pintype "passive"))
      (node (ref "DD1") (pin "2") (pinfunction "PC15-OSC32_OUT_2") (pintype "passive"))
      (node (ref "ZQ2") (pin "3") (pinfunction "3_3") (pintype "passive"))
    )
    (net (code "47") (name "Net-(VT1-G)") (class "Default")
      (node (ref "C31") (pin "1") (pinfunction "1_1") (pintype "passive"))
      (node (ref "R5") (pin "2") (pinfunction "2_2") (pintype "passive"))
      (node (ref "VT1") (pin "1") (pinfunction "G_1") (pintype "passive"))
    )
    (net (code "48") (name "Net-(VT1-S)") (class "Default")
      (node (ref "C31") (pin "2") (pinfunction "2_2") (pintype "passive"))
      (node (ref "R6") (pin "2") (pinfunction "2_2") (pintype "passive"))
      (node (ref "VT1") (pin "2") (pinfunction "S_2") (pintype "passive"))
    )
    (net (code "49") (name "Net-(ZQ1-OUT)") (class "Default")
      (node (ref "C3") (pin "1") (pinfunction "1_1") (pintype "passive"))
      (node (ref "ZQ1") (pin "3") (pinfunction "OUT_3") (pintype "passive"))
    )
    (net (code "50") (name "VCC_M") (class "Default")
      (node (ref "C10") (pin "1") (pinfunction "1_1") (pintype "passive"))
      (node (ref "C12") (pin "1") (pinfunction "1_1") (pintype "passive"))
      (node (ref "C14") (pin "1") (pinfunction "1_1") (pintype "passive"))
      (node (ref "C6") (pin "1") (pinfunction "1_1") (pintype "passive"))
      (node (ref "C8") (pin "1") (pinfunction "1_1") (pintype "passive"))
      (node (ref "DD1") (pin "17") (pinfunction "VDD_17") (pintype "power_in"))
      (node (ref "DD1") (pin "24") (pinfunction "VDDIO2_24") (pintype "power_in"))
      (node (ref "DD1") (pin "32") (pinfunction "VDD_32") (pintype "power_in"))
      (node (ref "DD1") (pin "5") (pinfunction "VDDA_5") (pintype "power_in"))
      (node (ref "R1") (pin "1") (pinfunction "1_1") (pintype "passive"))
      (node (ref "R6") (pin "1") (pinfunction "1_1") (pintype "passive"))
      (node (ref "XT12") (pin "1") (pinfunction "1_1") (pintype "passive"))
    )
    (net (code "51") (name "unconnected-(D1-BPSK_IN-Pad6)") (class "Default")
      (node (ref "D1") (pin "6") (pinfunction "BPSK_IN_6") (pintype "passive+no_connect"))
    )
    (net (code "52") (name "unconnected-(D1-DFT_EN-Pad7)") (class "Default")
      (node (ref "D1") (pin "7") (pinfunction "DFT_EN_7") (pintype "passive+no_connect"))
    )
    (net (code "53") (name "unconnected-(D1-NC-Pad1)") (class "Default")
      (node (ref "D1") (pin "1") (pinfunction "NC_1") (pintype "passive+no_connect"))
    )
    (net (code "54") (name "unconnected-(D1-NC-Pad16)") (class "Default")
      (node (ref "D1") (pin "16") (pinfunction "NC_16") (pintype "passive+no_connect"))
    )
    (net (code "55") (name "unconnected-(D1-TMUX2-Pad24)") (class "Default")
      (node (ref "D1") (pin "24") (pinfunction "TMUX2_24") (pintype "passive+no_connect"))
    )
    (net (code "56") (name "unconnected-(D1-TMUX3-Pad23)") (class "Default")
      (node (ref "D1") (pin "23") (pinfunction "TMUX3_23") (pintype "passive+no_connect"))
    )
    (net (code "57") (name "unconnected-(D1-TMUX4-Pad22)") (class "Default")
      (node (ref "D1") (pin "22") (pinfunction "TMUX4_22") (pintype "passive+no_connect"))
    )
    (net (code "58") (name "unconnected-(DA1-N{slash}C-Pad4)") (class "Default")
      (node (ref "DA1") (pin "4") (pinfunction "N/C_4") (pintype "passive+no_connect"))
    )
    (net (code "59") (name "unconnected-(E2-SHIELD-Pad1)") (class "Default")
      (node (ref "E2") (pin "1") (pinfunction "SHIELD_1") (pintype "passive+no_connect"))
    )
  )
)
